# 03-M2Finger.net
KiCad netlist of a schematic drawn in Altium Designer
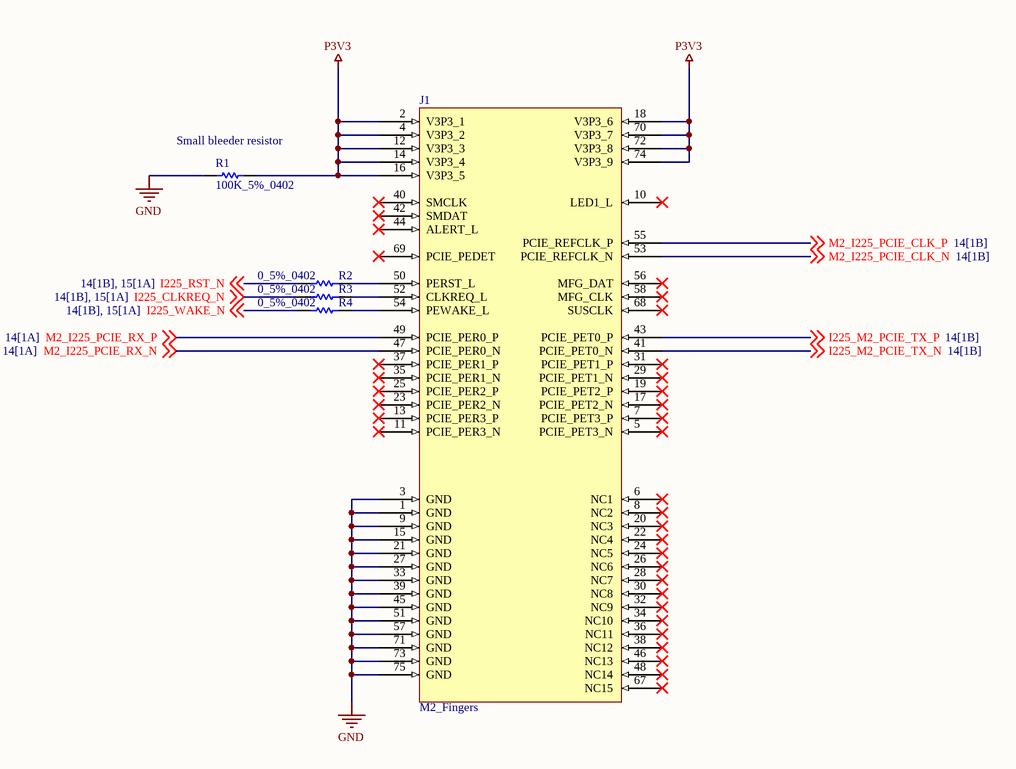
[diagram p0: 03-M2Finger.SchDoc]

(export (version "E")
  (design (tool "Eeschema 10.0.6"))
  (components
    (comp (ref "J1")
      (value "M2_Fingers")
      (footprint "M.2 PCIe fingers")
      (libsource (lib "TimeStick_Lib") (part "M2_Fingers"))
    )
    (comp (ref "R1")
      (value "100K_5%_0402")
      (footprint "RESC1005X40X25LL05T05")
      (fields (field (name "PART NUMBER") "CRCW0402100KJNED") (field (name "MANUFACTURER") "Vishay Dale"))
      (libsource (lib "Altium Content Vault") (part "RES"))
    )
    (comp (ref "R2")
      (value "0_5%_0402")
      (footprint "RESC1005X40X25LL10T10")
      (fields (field (name "MANUFACTURER") "KOA Speer") (field (name "PART NUMBER") "RK73Z1ETTP"))
      (libsource (lib "Altium Content Vault") (part "RES"))
    )
    (comp (ref "R3")
      (value "0_5%_0402")
      (footprint "RESC1005X40X25LL10T10")
      (fields (field (name "MANUFACTURER") "KOA Speer") (field (name "PART NUMBER") "RK73Z1ETTP"))
      (libsource (lib "Altium Content Vault") (part "RES"))
    )
    (comp (ref "R4")
      (value "0_5%_0402")
      (footprint "RESC1005X40X25LL10T10")
      (fields (field (name "MANUFACTURER") "KOA Speer") (field (name "PART NUMBER") "RK73Z1ETTP"))
      (libsource (lib "Altium Content Vault") (part "RES"))
    )
  )
  (nets
    (net (code "1") (name "GND") (class "Default")
      (node (ref "J1") (pin "1") (pinfunction "GND_1") (pintype "input"))
      (node (ref "J1") (pin "15") (pinfunction "GND_15") (pintype "input"))
      (node (ref "J1") (pin "21") (pinfunction "GND_21") (pintype "input"))
      (node (ref "J1") (pin "27") (pinfunction "GND_27") (pintype "input"))
      (node (ref "J1") (pin "3") (pinfunction "GND_3") (pintype "input"))
      (node (ref "J1") (pin "33") (pinfunction "GND_33") (pintype "input"))
      (node (ref "J1") (pin "39") (pinfunction "GND_39") (pintype "input"))
      (node (ref "J1") (pin "45") (pinfunction "GND_45") (pintype "input"))
      (node (ref "J1") (pin "51") (pinfunction "GND_51") (pintype "input"))
      (node (ref "J1") (pin "57") (pinfunction "GND_57") (pintype "input"))
      (node (ref "J1") (pin "71") (pinfunction "GND_71") (pintype "input"))
      (node (ref "J1") (pin "73") (pinfunction "GND_73") (pintype "input"))
      (node (ref "J1") (pin "75") (pinfunction "GND_75") (pintype "input"))
      (node (ref "J1") (pin "9") (pinfunction "GND_9") (pintype "input"))
      (node (ref "R1") (pin "1") (pinfunction "1_1") (pintype "passive"))
    )
    (net (code "2") (name "I225_CLKREQ_N") (class "Default")
      (node (ref "R3") (pin "1") (pinfunction "1_1") (pintype "passive"))
    )
    (net (code "3") (name "I225_M2_PCIE_TX_N") (class "Default")
      (node (ref "J1") (pin "41") (pinfunction "PCIE_PET0_N_41") (pintype "input"))
    )
    (net (code "4") (name "I225_M2_PCIE_TX_P") (class "Default")
      (node (ref "J1") (pin "43") (pinfunction "PCIE_PET0_P_43") (pintype "input"))
    )
    (net (code "5") (name "I225_RST_N") (class "Default")
      (node (ref "R2") (pin "1") (pinfunction "1_1") (pintype "passive"))
    )
    (net (code "6") (name "I225_WAKE_N") (class "Default")
      (node (ref "R4") (pin "1") (pinfunction "1_1") (pintype "passive"))
    )
    (net (code "7") (name "M2_I225_PCIE_CLK_N") (class "Default")
      (node (ref "J1") (pin "53") (pinfunction "PCIE_REFCLK_N_53") (pintype "input"))
    )
    (net (code "8") (name "M2_I225_PCIE_CLK_P") (class "Default")
      (node (ref "J1") (pin "55") (pinfunction "PCIE_REFCLK_P_55") (pintype "input"))
    )
    (net (code "9") (name "M2_I225_PCIE_RX_N") (class "Default")
      (node (ref "J1") (pin "47") (pinfunction "PCIE_PER0_N_47") (pintype "input"))
    )
    (net (code "10") (name "M2_I225_PCIE_RX_P") (class "Default")
      (node (ref "J1") (pin "49") (pinfunction "PCIE_PER0_P_49") (pintype "input"))
    )
    (net (code "11") (name "Net-(J1-CLKREQ_L)") (class "Default")
      (node (ref "J1") (pin "52") (pinfunction "CLKREQ_L_52") (pintype "input"))
      (node (ref "R3") (pin "2") (pinfunction "2_2") (pintype "passive"))
    )
    (net (code "12") (name "Net-(J1-PERST_L)") (class "Default")
      (node (ref "J1") (pin "50") (pinfunction "PERST_L_50") (pintype "input"))
      (node (ref "R2") (pin "2") (pinfunction "2_2") (pintype "passive"))
    )
    (net (code "13") (name "Net-(J1-PEWAKE_L)") (class "Default")
      (node (ref "J1") (pin "54") (pinfunction "PEWAKE_L_54") (pintype "input"))
      (node (ref "R4") (pin "2") (pinfunction "2_2") (pintype "passive"))
    )
    (net (code "14") (name "P3V3") (class "Default")
      (node (ref "J1") (pin "12") (pinfunction "V3P3_3_12") (pintype "input"))
      (node (ref "J1") (pin "14") (pinfunction "V3P3_4_14") (pintype "input"))
      (node (ref "J1") (pin "16") (pinfunction "V3P3_5_16") (pintype "input"))
      (node (ref "J1") (pin "18") (pinfunction "V3P3_6_18") (pintype "input"))
      (node (ref "J1") (pin "2") (pinfunction "V3P3_1_2") (pintype "input"))
      (node (ref "J1") (pin "4") (pinfunction "V3P3_2_4") (pintype "input"))
      (node (ref "J1") (pin "70") (pinfunction "V3P3_7_70") (pintype "input"))
      (node (ref "J1") (pin "72") (pinfunction "V3P3_8_72") (pintype "input"))
      (node (ref "J1") (pin "74") (pinfunction "V3P3_9_74") (pintype "input"))
      (node (ref "R1") (pin "2") (pinfunction "2_2") (pintype "passive"))
    )
    (net (code "15") (name "unconnected-(J1-ALERT_L-Pad44)") (class "Default")
      (node (ref "J1") (pin "44") (pinfunction "ALERT_L_44") (pintype "input+no_connect"))
    )
    (net (code "16") (name "unconnected-(J1-LED1_L-Pad10)") (class "Default")
      (node (ref "J1") (pin "10") (pinfunction "LED1_L_10") (pintype "input+no_connect"))
    )
    (net (code "17") (name "unconnected-(J1-MFG_CLK-Pad58)") (class "Default")
      (node (ref "J1") (pin "58") (pinfunction "MFG_CLK_58") (pintype "input+no_connect"))
    )
    (net (code "18") (name "unconnected-(J1-MFG_DAT-Pad56)") (class "Default")
      (node (ref "J1") (pin "56") (pinfunction "MFG_DAT_56") (pintype "input+no_connect"))
    )
    (net (code "19") (name "unconnected-(J1-NC1-Pad6)") (class "Default")
      (node (ref "J1") (pin "6") (pinfunction "NC1_6") (pintype "input+no_connect"))
    )
    (net (code "20") (name "unconnected-(J1-NC2-Pad8)") (class "Default")
      (node (ref "J1") (pin "8") (pinfunction "NC2_8") (pintype "input+no_connect"))
    )
    (net (code "21") (name "unconnected-(J1-NC3-Pad20)") (class "Default")
      (node (ref "J1") (pin "20") (pinfunction "NC3_20") (pintype "input+no_connect"))
    )
    (net (code "22") (name "unconnected-(J1-NC4-Pad22)") (class "Default")
      (node (ref "J1") (pin "22") (pinfunction "NC4_22") (pintype "input+no_connect"))
    )
    (net (code "23") (name "unconnected-(J1-NC5-Pad24)") (class "Default")
      (node (ref "J1") (pin "24") (pinfunction "NC5_24") (pintype "input+no_connect"))
    )
    (net (code "24") (name "unconnected-(J1-NC6-Pad26)") (class "Default")
      (node (ref "J1") (pin "26") (pinfunction "NC6_26") (pintype "input+no_connect"))
    )
    (net (code "25") (name "unconnected-(J1-NC7-Pad28)") (class "Default")
      (node (ref "J1") (pin "28") (pinfunction "NC7_28") (pintype "input+no_connect"))
    )
    (net (code "26") (name "unconnected-(J1-NC8-Pad30)") (class "Default")
      (node (ref "J1") (pin "30") (pinfunction "NC8_30") (pintype "input+no_connect"))
    )
    (net (code "27") (name "unconnected-(J1-NC9-Pad32)") (class "Default")
      (node (ref "J1") (pin "32") (pinfunction "NC9_32") (pintype "input+no_connect"))
    )
    (net (code "28") (name "unconnected-(J1-NC10-Pad34)") (class "Default")
      (node (ref "J1") (pin "34") (pinfunction "NC10_34") (pintype "input+no_connect"))
    )
    (net (code "29") (name "unconnected-(J1-NC11-Pad36)") (class "Default")
      (node (ref "J1") (pin "36") (pinfunction "NC11_36") (pintype "input+no_connect"))
    )
    (net (code "30") (name "unconnected-(J1-NC12-Pad38)") (class "Default")
      (node (ref "J1") (pin "38") (pinfunction "NC12_38") (pintype "input+no_connect"))
    )
    (net (code "31") (name "unconnected-(J1-NC13-Pad46)") (class "Default")
      (node (ref "J1") (pin "46") (pinfunction "NC13_46") (pintype "input+no_connect"))
    )
    (net (code "32") (name "unconnected-(J1-NC14-Pad48)") (class "Default")
      (node (ref "J1") (pin "48") (pinfunction "NC14_48") (pintype "input+no_connect"))
    )
    (net (code "33") (name "unconnected-(J1-NC15-Pad67)") (class "Default")
      (node (ref "J1") (pin "67") (pinfunction "NC15_67") (pintype "input+no_connect"))
    )
    (net (code "34") (name "unconnected-(J1-PCIE_PEDET-Pad69)") (class "Default")
      (node (ref "J1") (pin "69") (pinfunction "PCIE_PEDET_69") (pintype "input+no_connect"))
    )
    (net (code "35") (name "unconnected-(J1-PCIE_PER1_N-Pad35)") (class "Default")
      (node (ref "J1") (pin "35") (pinfunction "PCIE_PER1_N_35") (pintype "input+no_connect"))
    )
    (net (code "36") (name "unconnected-(J1-PCIE_PER1_P-Pad37)") (class "Default")
      (node (ref "J1") (pin "37") (pinfunction "PCIE_PER1_P_37") (pintype "input+no_connect"))
    )
    (net (code "37") (name "unconnected-(J1-PCIE_PER2_N-Pad23)") (class "Default")
      (node (ref "J1") (pin "23") (pinfunction "PCIE_PER2_N_23") (pintype "input+no_connect"))
    )
    (net (code "38") (name "unconnected-(J1-PCIE_PER2_P-Pad25)") (class "Default")
      (node (ref "J1") (pin "25") (pinfunction "PCIE_PER2_P_25") (pintype "input+no_connect"))
    )
    (net (code "39") (name "unconnected-(J1-PCIE_PER3_N-Pad11)") (class "Default")
      (node (ref "J1") (pin "11") (pinfunction "PCIE_PER3_N_11") (pintype "input+no_connect"))
    )
    (net (code "40") (name "unconnected-(J1-PCIE_PER3_P-Pad13)") (class "Default")
      (node (ref "J1") (pin "13") (pinfunction "PCIE_PER3_P_13") (pintype "input+no_connect"))
    )
    (net (code "41") (name "unconnected-(J1-PCIE_PET1_N-Pad29)") (class "Default")
      (node (ref "J1") (pin "29") (pinfunction "PCIE_PET1_N_29") (pintype "input+no_connect"))
    )
    (net (code "42") (name "unconnected-(J1-PCIE_PET1_P-Pad31)") (class "Default")
      (node (ref "J1") (pin "31") (pinfunction "PCIE_PET1_P_31") (pintype "input+no_connect"))
    )
    (net (code "43") (name "unconnected-(J1-PCIE_PET2_N-Pad17)") (class "Default")
      (node (ref "J1") (pin "17") (pinfunction "PCIE_PET2_N_17") (pintype "input+no_connect"))
    )
    (net (code "44") (name "unconnected-(J1-PCIE_PET2_P-Pad19)") (class "Default")
      (node (ref "J1") (pin "19") (pinfunction "PCIE_PET2_P_19") (pintype "input+no_connect"))
    )
    (net (code "45") (name "unconnected-(J1-PCIE_PET3_N-Pad5)") (class "Default")
      (node (ref "J1") (pin "5") (pinfunction "PCIE_PET3_N_5") (pintype "input+no_connect"))
    )
    (net (code "46") (name "unconnected-(J1-PCIE_PET3_P-Pad7)") (class "Default")
      (node (ref "J1") (pin "7") (pinfunction "PCIE_PET3_P_7") (pintype "input+no_connect"))
    )
    (net (code "47") (name "unconnected-(J1-SMCLK-Pad40)") (class "Default")
      (node (ref "J1") (pin "40") (pinfunction "SMCLK_40") (pintype "input+no_connect"))
    )
    (net (code "48") (name "unconnected-(J1-SMDAT-Pad42)") (class "Default")
      (node (ref "J1") (pin "42") (pinfunction "SMDAT_42") (pintype "input+no_connect"))
    )
    (net (code "49") (name "unconnected-(J1-SUSCLK-Pad68)") (class "Default")
      (node (ref "J1") (pin "68") (pinfunction "SUSCLK_68") (pintype "input+no_connect"))
    )
  )
)
